# Sheet1.net
KiCad netlist of a schematic drawn in Altium Designer
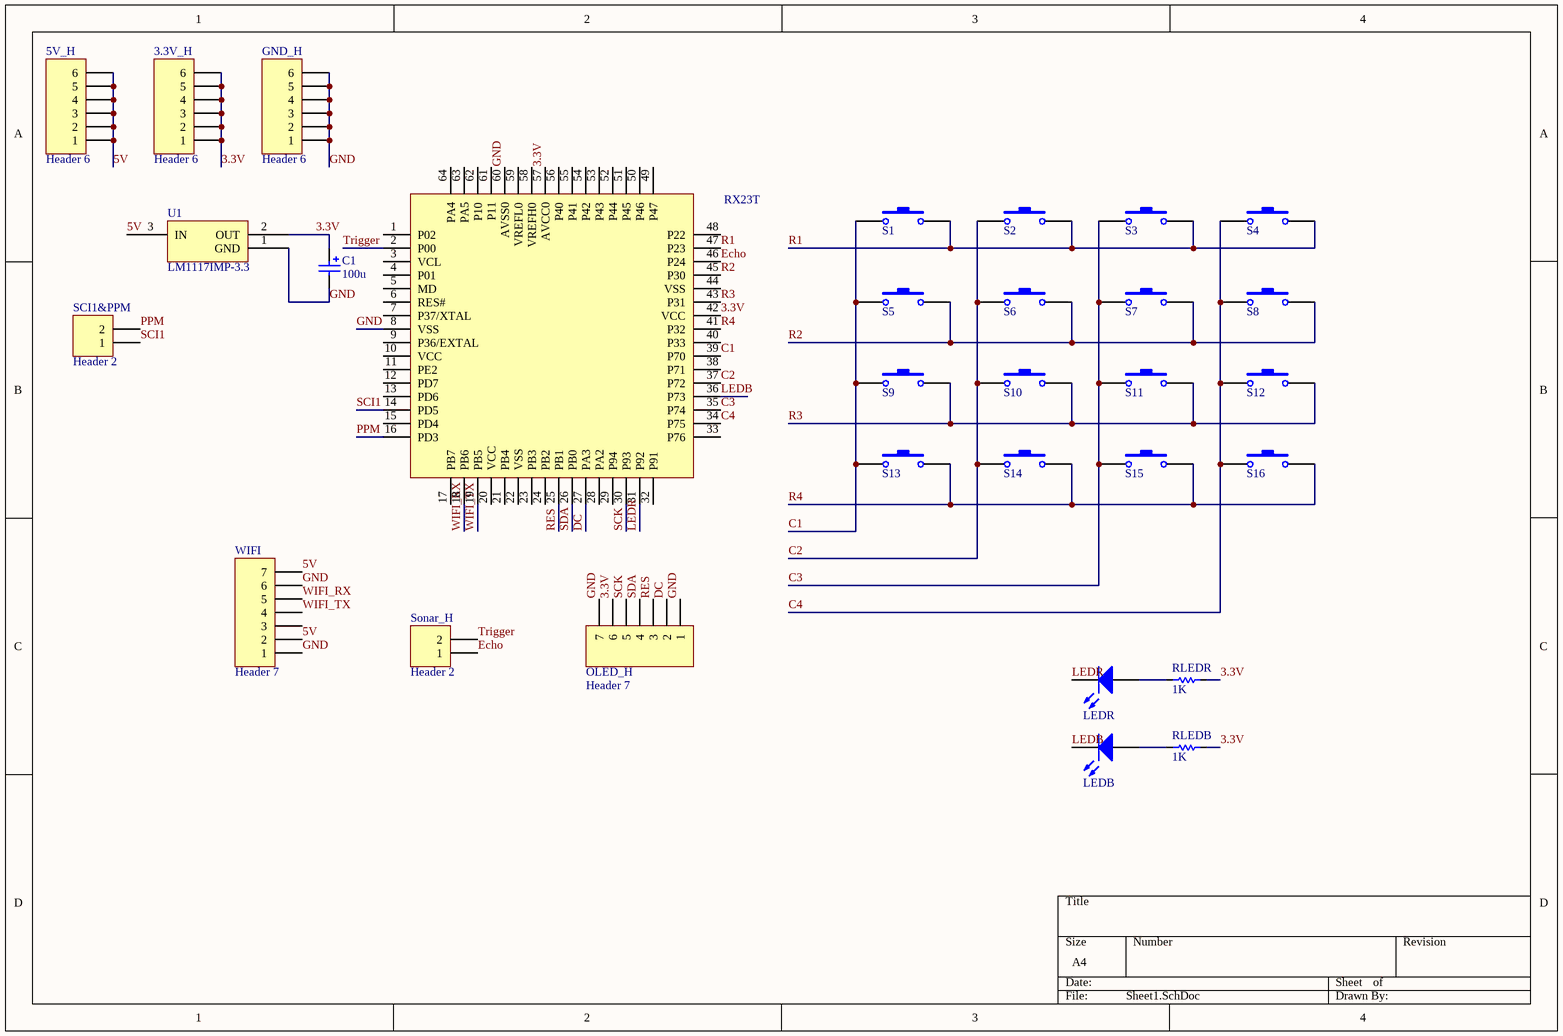
[diagram p0: Sheet1.SchDoc]

(export (version "E")
  (design (tool "Eeschema 10.0.6"))
  (components
    (comp (ref "3.3V_H")
      (value "Header 6")
      (footprint "HDR1X6")
      (description "Header, 6-Pin")
      (fields (field (name "PUBLISHER") "Altium Limited"))
      (libsource (lib "Miscellaneous Connectors") (part "Header 6"))
    )
    (comp (ref "5V_H")
      (value "Header 6")
      (footprint "HDR1X6")
      (description "Header, 6-Pin")
      (fields (field (name "PUBLISHER") "Altium Limited"))
      (libsource (lib "Miscellaneous Connectors") (part "Header 6"))
    )
    (comp (ref "C1")
      (value "100u")
      (footprint "CAP 2.5*5*11")
      (description "Polarized Capacitor (Surface Mount)")
      (fields (field (name "Comment") "Cap Pol3") (field (name "PUBLISHER") "Altium Limited"))
      (libsource (lib "RX23T") (part "Cap Pol3"))
    )
    (comp (ref "GND_H")
      (value "Header 6")
      (footprint "HDR1X6")
      (description "Header, 6-Pin")
      (fields (field (name "PUBLISHER") "Altium Limited"))
      (libsource (lib "Miscellaneous Connectors") (part "Header 6"))
    )
    (comp (ref "LEDB") (value "LED") (footprint "LED 3MM-R") (libsource (lib "RX23T") (part "LED")))
    (comp (ref "LEDR") (value "LED") (footprint "LED 3MM-R") (libsource (lib "RX23T") (part "LED")))
    (comp (ref "OLED_H")
      (value "Header 7")
      (footprint "HDR1X7")
      (description "Header, 7-Pin")
      (fields (field (name "PUBLISHER") "Altium Limited"))
      (libsource (lib "") (part "Header 7_1"))
    )
    (comp (ref "RLEDB")
      (value "1K")
      (footprint "RS 1/4W")
      (description "R_0603")
      (libsource (lib "RX23T") (part "R"))
    )
    (comp (ref "RLEDR")
      (value "1K")
      (footprint "RS 1/4W")
      (description "R_0603")
      (libsource (lib "RX23T") (part "R"))
    )
    (comp (ref "RX23T") (value "RX23T") (footprint "RFR") (libsource (lib "RX23T") (part "RX23T")))
    (comp (ref "S1") (value "贴片轻触开关") (footprint "SW-6*6") (libsource (lib "RX23T") (part "贴片轻触开关")))
    (comp (ref "S2") (value "贴片轻触开关") (footprint "SW-6*6") (libsource (lib "RX23T") (part "贴片轻触开关")))
    (comp (ref "S3") (value "贴片轻触开关") (footprint "SW-6*6") (libsource (lib "RX23T") (part "贴片轻触开关")))
    (comp (ref "S4") (value "贴片轻触开关") (footprint "SW-6*6") (libsource (lib "RX23T") (part "贴片轻触开关")))
    (comp (ref "S5") (value "贴片轻触开关") (footprint "SW-6*6") (libsource (lib "RX23T") (part "贴片轻触开关")))
    (comp (ref "S6") (value "贴片轻触开关") (footprint "SW-6*6") (libsource (lib "RX23T") (part "贴片轻触开关")))
    (comp (ref "S7") (value "贴片轻触开关") (footprint "SW-6*6") (libsource (lib "RX23T") (part "贴片轻触开关")))
    (comp (ref "S8") (value "贴片轻触开关") (footprint "SW-6*6") (libsource (lib "RX23T") (part "贴片轻触开关")))
    (comp (ref "S9") (value "贴片轻触开关") (footprint "SW-6*6") (libsource (lib "RX23T") (part "贴片轻触开关")))
    (comp (ref "S10") (value "贴片轻触开关") (footprint "SW-6*6") (libsource (lib "RX23T") (part "贴片轻触开关")))
    (comp (ref "S11") (value "贴片轻触开关") (footprint "SW-6*6") (libsource (lib "RX23T") (part "贴片轻触开关")))
    (comp (ref "S12") (value "贴片轻触开关") (footprint "SW-6*6") (libsource (lib "RX23T") (part "贴片轻触开关")))
    (comp (ref "S13") (value "贴片轻触开关") (footprint "SW-6*6") (libsource (lib "RX23T") (part "贴片轻触开关")))
    (comp (ref "S14") (value "贴片轻触开关") (footprint "SW-6*6") (libsource (lib "RX23T") (part "贴片轻触开关")))
    (comp (ref "S15") (value "贴片轻触开关") (footprint "SW-6*6") (libsource (lib "RX23T") (part "贴片轻触开关")))
    (comp (ref "S16") (value "贴片轻触开关") (footprint "SW-6*6") (libsource (lib "RX23T") (part "贴片轻触开关")))
    (comp (ref "SCI1&PPM")
      (value "Header 2")
      (footprint "HDR1X2")
      (description "Header, 2-Pin")
      (fields (field (name "PUBLISHER") "Altium Limited"))
      (libsource (lib "Miscellaneous Connectors") (part "Header 2"))
    )
    (comp (ref "Sonar_H")
      (value "Header 2")
      (footprint "HDR1X2")
      (description "Header, 2-Pin")
      (fields (field (name "PUBLISHER") "Altium Limited"))
      (libsource (lib "Miscellaneous Connectors") (part "Header 2"))
    )
    (comp (ref "U1")
      (value "LM1117IMP-3.3")
      (footprint "SOT223_M")
      (libsource (lib "RX23T") (part "Component_1_1"))
    )
    (comp (ref "WIFI")
      (value "Header 7")
      (footprint "HDR1X7")
      (description "Header, 7-Pin")
      (fields (field (name "PUBLISHER") "Altium Limited"))
      (libsource (lib "Miscellaneous Connectors") (part "Header 7"))
    )
  )
  (nets
    (net (code "1") (name "/3.3V") (class "Default")
      (node (ref "3.3V_H") (pin "1") (pinfunction "1_1") (pintype "passive"))
      (node (ref "3.3V_H") (pin "2") (pinfunction "2_2") (pintype "passive"))
      (node (ref "3.3V_H") (pin "3") (pinfunction "3_3") (pintype "passive"))
      (node (ref "3.3V_H") (pin "4") (pinfunction "4_4") (pintype "passive"))
      (node (ref "3.3V_H") (pin "5") (pinfunction "5_5") (pintype "passive"))
      (node (ref "3.3V_H") (pin "6") (pinfunction "6_6") (pintype "passive"))
      (node (ref "C1") (pin "1") (pinfunction "1_1") (pintype "passive"))
      (node (ref "OLED_H") (pin "6") (pinfunction "6_6") (pintype "passive"))
      (node (ref "RLEDB") (pin "2") (pinfunction "2_2") (pintype "passive"))
      (node (ref "RLEDR") (pin "2") (pinfunction "2_2") (pintype "passive"))
      (node (ref "RX23T") (pin "42") (pinfunction "VCC_42") (pintype "passive"))
      (node (ref "RX23T") (pin "57") (pinfunction "AVCC0_57") (pintype "passive"))
      (node (ref "U1") (pin "2") (pinfunction "OUT_2") (pintype "passive"))
    )
    (net (code "2") (name "/5V") (class "Default")
      (node (ref "5V_H") (pin "1") (pinfunction "1_1") (pintype "passive"))
      (node (ref "5V_H") (pin "2") (pinfunction "2_2") (pintype "passive"))
      (node (ref "5V_H") (pin "3") (pinfunction "3_3") (pintype "passive"))
      (node (ref "5V_H") (pin "4") (pinfunction "4_4") (pintype "passive"))
      (node (ref "5V_H") (pin "5") (pinfunction "5_5") (pintype "passive"))
      (node (ref "5V_H") (pin "6") (pinfunction "6_6") (pintype "passive"))
      (node (ref "U1") (pin "3") (pinfunction "IN_3") (pintype "passive"))
      (node (ref "WIFI") (pin "2") (pinfunction "2_2") (pintype "passive"))
      (node (ref "WIFI") (pin "7") (pinfunction "7_7") (pintype "passive"))
    )
    (net (code "3") (name "/C1") (class "Default")
      (node (ref "RX23T") (pin "39") (pinfunction "P70_39") (pintype "passive"))
      (node (ref "S1") (pin "1") (pinfunction "1_1") (pintype "passive"))
      (node (ref "S13") (pin "1") (pinfunction "1_1") (pintype "passive"))
      (node (ref "S5") (pin "1") (pinfunction "1_1") (pintype "passive"))
      (node (ref "S9") (pin "1") (pinfunction "1_1") (pintype "passive"))
    )
    (net (code "4") (name "/C2") (class "Default")
      (node (ref "RX23T") (pin "37") (pinfunction "P72_37") (pintype "passive"))
      (node (ref "S10") (pin "1") (pinfunction "1_1") (pintype "passive"))
      (node (ref "S14") (pin "1") (pinfunction "1_1") (pintype "passive"))
      (node (ref "S2") (pin "1") (pinfunction "1_1") (pintype "passive"))
      (node (ref "S6") (pin "1") (pinfunction "1_1") (pintype "passive"))
    )
    (net (code "5") (name "/C3") (class "Default")
      (node (ref "RX23T") (pin "35") (pinfunction "P74_35") (pintype "passive"))
      (node (ref "S11") (pin "1") (pinfunction "1_1") (pintype "passive"))
      (node (ref "S15") (pin "1") (pinfunction "1_1") (pintype "passive"))
      (node (ref "S3") (pin "1") (pinfunction "1_1") (pintype "passive"))
      (node (ref "S7") (pin "1") (pinfunction "1_1") (pintype "passive"))
    )
    (net (code "6") (name "/C4") (class "Default")
      (node (ref "RX23T") (pin "34") (pinfunction "P75_34") (pintype "passive"))
      (node (ref "S12") (pin "1") (pinfunction "1_1") (pintype "passive"))
      (node (ref "S16") (pin "1") (pinfunction "1_1") (pintype "passive"))
      (node (ref "S4") (pin "1") (pinfunction "1_1") (pintype "passive"))
      (node (ref "S8") (pin "1") (pinfunction "1_1") (pintype "passive"))
    )
    (net (code "7") (name "/DC") (class "Default")
      (node (ref "OLED_H") (pin "2") (pinfunction "2_2") (pintype "passive"))
      (node (ref "RX23T") (pin "27") (pinfunction "PA3_27") (pintype "passive"))
    )
    (net (code "8") (name "/Echo") (class "Default")
      (node (ref "RX23T") (pin "46") (pinfunction "P24_46") (pintype "passive"))
      (node (ref "Sonar_H") (pin "1") (pinfunction "1_1") (pintype "passive"))
    )
    (net (code "9") (name "/GND") (class "Default")
      (node (ref "C1") (pin "2") (pinfunction "2_2") (pintype "passive"))
      (node (ref "GND_H") (pin "1") (pinfunction "1_1") (pintype "passive"))
      (node (ref "GND_H") (pin "2") (pinfunction "2_2") (pintype "passive"))
      (node (ref "GND_H") (pin "3") (pinfunction "3_3") (pintype "passive"))
      (node (ref "GND_H") (pin "4") (pinfunction "4_4") (pintype "passive"))
      (node (ref "GND_H") (pin "5") (pinfunction "5_5") (pintype "passive"))
      (node (ref "GND_H") (pin "6") (pinfunction "6_6") (pintype "passive"))
      (node (ref "OLED_H") (pin "1") (pinfunction "1_1") (pintype "passive"))
      (node (ref "OLED_H") (pin "7") (pinfunction "7_7") (pintype "passive"))
      (node (ref "RX23T") (pin "60") (pinfunction "AVSS0_60") (pintype "passive"))
      (node (ref "RX23T") (pin "8") (pinfunction "VSS_8") (pintype "passive"))
      (node (ref "U1") (pin "1") (pinfunction "GND_1") (pintype "passive"))
      (node (ref "WIFI") (pin "1") (pinfunction "1_1") (pintype "passive"))
      (node (ref "WIFI") (pin "6") (pinfunction "6_6") (pintype "passive"))
    )
    (net (code "10") (name "/LEDB") (class "Default")
      (node (ref "LEDB") (pin "2") (pinfunction "2_2") (pintype "passive"))
      (node (ref "RX23T") (pin "36") (pinfunction "P73_36") (pintype "passive"))
    )
    (net (code "11") (name "/LEDR") (class "Default")
      (node (ref "LEDR") (pin "2") (pinfunction "2_2") (pintype "passive"))
      (node (ref "RX23T") (pin "31") (pinfunction "P92_31") (pintype "passive"))
    )
    (net (code "12") (name "/PPM") (class "Default")
      (node (ref "RX23T") (pin "16") (pinfunction "PD3_16") (pintype "passive"))
      (node (ref "SCI1&PPM") (pin "2") (pinfunction "2_2") (pintype "passive"))
    )
    (net (code "13") (name "/R1") (class "Default")
      (node (ref "RX23T") (pin "47") (pinfunction "P23_47") (pintype "passive"))
      (node (ref "S1") (pin "2") (pinfunction "2_2") (pintype "passive"))
      (node (ref "S2") (pin "2") (pinfunction "2_2") (pintype "passive"))
      (node (ref "S3") (pin "2") (pinfunction "2_2") (pintype "passive"))
      (node (ref "S4") (pin "2") (pinfunction "2_2") (pintype "passive"))
    )
    (net (code "14") (name "/R2") (class "Default")
      (node (ref "RX23T") (pin "45") (pinfunction "P30_45") (pintype "passive"))
      (node (ref "S5") (pin "2") (pinfunction "2_2") (pintype "passive"))
      (node (ref "S6") (pin "2") (pinfunction "2_2") (pintype "passive"))
      (node (ref "S7") (pin "2") (pinfunction "2_2") (pintype "passive"))
      (node (ref "S8") (pin "2") (pinfunction "2_2") (pintype "passive"))
    )
    (net (code "15") (name "/R3") (class "Default")
      (node (ref "RX23T") (pin "43") (pinfunction "P31_43") (pintype "passive"))
      (node (ref "S10") (pin "2") (pinfunction "2_2") (pintype "passive"))
      (node (ref "S11") (pin "2") (pinfunction "2_2") (pintype "passive"))
      (node (ref "S12") (pin "2") (pinfunction "2_2") (pintype "passive"))
      (node (ref "S9") (pin "2") (pinfunction "2_2") (pintype "passive"))
    )
    (net (code "16") (name "/R4") (class "Default")
      (node (ref "RX23T") (pin "41") (pinfunction "P32_41") (pintype "passive"))
      (node (ref "S13") (pin "2") (pinfunction "2_2") (pintype "passive"))
      (node (ref "S14") (pin "2") (pinfunction "2_2") (pintype "passive"))
      (node (ref "S15") (pin "2") (pinfunction "2_2") (pintype "passive"))
      (node (ref "S16") (pin "2") (pinfunction "2_2") (pintype "passive"))
    )
    (net (code "17") (name "/RES") (class "Default")
      (node (ref "OLED_H") (pin "3") (pinfunction "3_3") (pintype "passive"))
      (node (ref "RX23T") (pin "25") (pinfunction "PB1_25") (pintype "passive"))
    )
    (net (code "18") (name "/SCI1") (class "Default")
      (node (ref "RX23T") (pin "14") (pinfunction "PD5_14") (pintype "passive"))
      (node (ref "SCI1&PPM") (pin "1") (pinfunction "1_1") (pintype "passive"))
    )
    (net (code "19") (name "/SCK") (class "Default")
      (node (ref "OLED_H") (pin "5") (pinfunction "5_5") (pintype "passive"))
      (node (ref "RX23T") (pin "30") (pinfunction "P93_30") (pintype "passive"))
    )
    (net (code "20") (name "/SDA") (class "Default")
      (node (ref "OLED_H") (pin "4") (pinfunction "4_4") (pintype "passive"))
      (node (ref "RX23T") (pin "26") (pinfunction "PB0_26") (pintype "passive"))
    )
    (net (code "21") (name "/Trigger") (class "Default")
      (node (ref "RX23T") (pin "2") (pinfunction "P00_2") (pintype "passive"))
      (node (ref "Sonar_H") (pin "2") (pinfunction "2_2") (pintype "passive"))
    )
    (net (code "22") (name "/WIFI_RX") (class "Default")
      (node (ref "RX23T") (pin "18") (pinfunction "PB6_18") (pintype "passive"))
      (node (ref "WIFI") (pin "5") (pinfunction "5_5") (pintype "passive"))
    )
    (net (code "23") (name "/WIFI_TX") (class "Default")
      (node (ref "RX23T") (pin "19") (pinfunction "PB5_19") (pintype "passive"))
      (node (ref "WIFI") (pin "4") (pinfunction "4_4") (pintype "passive"))
    )
    (net (code "24") (name "Net-(LEDB-Pad1)") (class "Default")
      (node (ref "LEDB") (pin "1") (pinfunction "1_1") (pintype "passive"))
      (node (ref "RLEDB") (pin "1") (pinfunction "1_1") (pintype "passive"))
    )
    (net (code "25") (name "Net-(LEDR-Pad1)") (class "Default")
      (node (ref "LEDR") (pin "1") (pinfunction "1_1") (pintype "passive"))
      (node (ref "RLEDR") (pin "1") (pinfunction "1_1") (pintype "passive"))
    )
    (net (code "26") (name "unconnected-(RX23T-MD-Pad5)") (class "Default")
      (node (ref "RX23T") (pin "5") (pinfunction "MD_5") (pintype "passive"))
    )
    (net (code "27") (name "unconnected-(RX23T-P01-Pad4)") (class "Default")
      (node (ref "RX23T") (pin "4") (pinfunction "P01_4") (pintype "passive"))
    )
    (net (code "28") (name "unconnected-(RX23T-P02-Pad1)") (class "Default")
      (node (ref "RX23T") (pin "1") (pinfunction "P02_1") (pintype "passive"))
    )
    (net (code "29") (name "unconnected-(RX23T-P10-Pad62)") (class "Default")
      (node (ref "RX23T") (pin "62") (pinfunction "P10_62") (pintype "passive"))
    )
    (net (code "30") (name "unconnected-(RX23T-P11-Pad61)") (class "Default")
      (node (ref "RX23T") (pin "61") (pinfunction "P11_61") (pintype "passive"))
    )
    (net (code "31") (name "unconnected-(RX23T-P22-Pad48)") (class "Default")
      (node (ref "RX23T") (pin "48") (pinfunction "P22_48") (pintype "passive"))
    )
    (net (code "32") (name "unconnected-(RX23T-P33-Pad40)") (class "Default")
      (node (ref "RX23T") (pin "40") (pinfunction "P33_40") (pintype "passive"))
    )
    (net (code "33") (name "unconnected-(RX23T-P36{slash}EXTAL-Pad9)") (class "Default")
      (node (ref "RX23T") (pin "9") (pinfunction "P36/EXTAL_9") (pintype "passive"))
    )
    (net (code "34") (name "unconnected-(RX23T-P37{slash}XTAL-Pad7)") (class "Default")
      (node (ref "RX23T") (pin "7") (pinfunction "P37/XTAL_7") (pintype "passive"))
    )
    (net (code "35") (name "unconnected-(RX23T-P40-Pad56)") (class "Default")
      (node (ref "RX23T") (pin "56") (pinfunction "P40_56") (pintype "passive"))
    )
    (net (code "36") (name "unconnected-(RX23T-P41-Pad55)") (class "Default")
      (node (ref "RX23T") (pin "55") (pinfunction "P41_55") (pintype "passive"))
    )
    (net (code "37") (name "unconnected-(RX23T-P42-Pad54)") (class "Default")
      (node (ref "RX23T") (pin "54") (pinfunction "P42_54") (pintype "passive"))
    )
    (net (code "38") (name "unconnected-(RX23T-P43-Pad53)") (class "Default")
      (node (ref "RX23T") (pin "53") (pinfunction "P43_53") (pintype "passive"))
    )
    (net (code "39") (name "unconnected-(RX23T-P44-Pad52)") (class "Default")
      (node (ref "RX23T") (pin "52") (pinfunction "P44_52") (pintype "passive"))
    )
    (net (code "40") (name "unconnected-(RX23T-P45-Pad51)") (class "Default")
      (node (ref "RX23T") (pin "51") (pinfunction "P45_51") (pintype "passive"))
    )
    (net (code "41") (name "unconnected-(RX23T-P46-Pad50)") (class "Default")
      (node (ref "RX23T") (pin "50") (pinfunction "P46_50") (pintype "passive"))
    )
    (net (code "42") (name "unconnected-(RX23T-P47-Pad49)") (class "Default")
      (node (ref "RX23T") (pin "49") (pinfunction "P47_49") (pintype "passive"))
    )
    (net (code "43") (name "unconnected-(RX23T-P71-Pad38)") (class "Default")
      (node (ref "RX23T") (pin "38") (pinfunction "P71_38") (pintype "passive"))
    )
    (net (code "44") (name "unconnected-(RX23T-P76-Pad33)") (class "Default")
      (node (ref "RX23T") (pin "33") (pinfunction "P76_33") (pintype "passive"))
    )
    (net (code "45") (name "unconnected-(RX23T-P91-Pad32)") (class "Default")
      (node (ref "RX23T") (pin "32") (pinfunction "P91_32") (pintype "passive"))
    )
    (net (code "46") (name "unconnected-(RX23T-P94-Pad29)") (class "Default")
      (node (ref "RX23T") (pin "29") (pinfunction "P94_29") (pintype "passive"))
    )
    (net (code "47") (name "unconnected-(RX23T-PA2-Pad28)") (class "Default")
      (node (ref "RX23T") (pin "28") (pinfunction "PA2_28") (pintype "passive"))
    )
    (net (code "48") (name "unconnected-(RX23T-PA4-Pad64)") (class "Default")
      (node (ref "RX23T") (pin "64") (pinfunction "PA4_64") (pintype "passive"))
    )
    (net (code "49") (name "unconnected-(RX23T-PA5-Pad63)") (class "Default")
      (node (ref "RX23T") (pin "63") (pinfunction "PA5_63") (pintype "passive"))
    )
    (net (code "50") (name "unconnected-(RX23T-PB2-Pad24)") (class "Default")
      (node (ref "RX23T") (pin "24") (pinfunction "PB2_24") (pintype "passive"))
    )
    (net (code "51") (name "unconnected-(RX23T-PB3-Pad23)") (class "Default")
      (node (ref "RX23T") (pin "23") (pinfunction "PB3_23") (pintype "passive"))
    )
    (net (code "52") (name "unconnected-(RX23T-PB4-Pad21)") (class "Default")
      (node (ref "RX23T") (pin "21") (pinfunction "PB4_21") (pintype "passive"))
    )
    (net (code "53") (name "unconnected-(RX23T-PB7-Pad17)") (class "Default")
      (node (ref "RX23T") (pin "17") (pinfunction "PB7_17") (pintype "passive"))
    )
    (net (code "54") (name "unconnected-(RX23T-PD4-Pad15)") (class "Default")
      (node (ref "RX23T") (pin "15") (pinfunction "PD4_15") (pintype "passive"))
    )
    (net (code "55") (name "unconnected-(RX23T-PD6-Pad13)") (class "Default")
      (node (ref "RX23T") (pin "13") (pinfunction "PD6_13") (pintype "passive"))
    )
    (net (code "56") (name "unconnected-(RX23T-PD7-Pad12)") (class "Default")
      (node (ref "RX23T") (pin "12") (pinfunction "PD7_12") (pintype "passive"))
    )
    (net (code "57") (name "unconnected-(RX23T-PE2-Pad11)") (class "Default")
      (node (ref "RX23T") (pin "11") (pinfunction "PE2_11") (pintype "passive"))
    )
    (net (code "58") (name "unconnected-(RX23T-RES#-Pad6)") (class "Default")
      (node (ref "RX23T") (pin "6") (pinfunction "RES#_6") (pintype "passive"))
    )
    (net (code "59") (name "unconnected-(RX23T-VCC-Pad10)") (class "Default")
      (node (ref "RX23T") (pin "10") (pinfunction "VCC_10") (pintype "passive"))
    )
    (net (code "60") (name "unconnected-(RX23T-VCC-Pad20)") (class "Default")
      (node (ref "RX23T") (pin "20") (pinfunction "VCC_20") (pintype "passive"))
    )
    (net (code "61") (name "unconnected-(RX23T-VCL-Pad3)") (class "Default")
      (node (ref "RX23T") (pin "3") (pinfunction "VCL_3") (pintype "passive"))
    )
    (net (code "62") (name "unconnected-(RX23T-VREFH0-Pad58)") (class "Default")
      (node (ref "RX23T") (pin "58") (pinfunction "VREFH0_58") (pintype "passive"))
    )
    (net (code "63") (name "unconnected-(RX23T-VREFL0-Pad59)") (class "Default")
      (node (ref "RX23T") (pin "59") (pinfunction "VREFL0_59") (pintype "passive"))
    )
    (net (code "64") (name "unconnected-(RX23T-VSS-Pad22)") (class "Default")
      (node (ref "RX23T") (pin "22") (pinfunction "VSS_22") (pintype "passive"))
    )
    (net (code "65") (name "unconnected-(RX23T-VSS-Pad44)") (class "Default")
      (node (ref "RX23T") (pin "44") (pinfunction "VSS_44") (pintype "passive"))
    )
    (net (code "66") (name "unconnected-(WIFI-Pad3)") (class "Default")
      (node (ref "WIFI") (pin "3") (pinfunction "3_3") (pintype "passive"))
    )
  )
)
